# Superbot_USB.net
KiCad netlist of a schematic drawn in Altium Designer
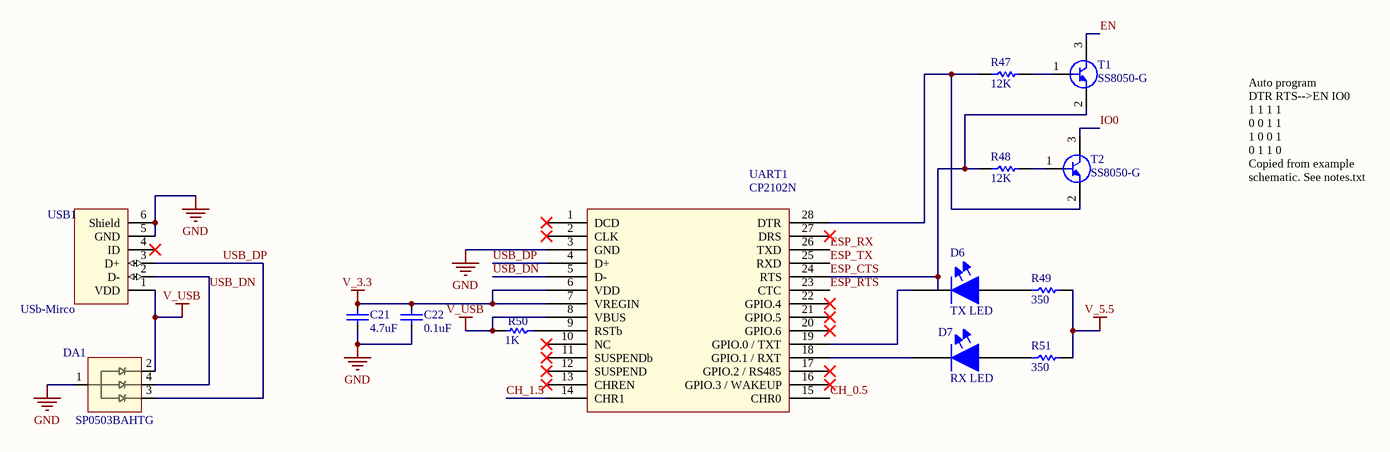
[diagram p0: Superbot_USB.SchDoc]

(export (version "E")
  (design (tool "Eeschema 10.0.6"))
  (components
    (comp (ref "C21")
      (value "4.7uF")
      (footprint "CAP0603R")
      (description "Capacitor")
      (fields
        (field (name "MANUFACTURER") "Microchip Technology")
        (field (name "MANUFACTURER PART NUM") "MIC5378YC5-TR")
      )
      (libsource (lib "SuperBot_Schlib1") (part "C"))
    )
    (comp (ref "C22")
      (value "0.1uF")
      (footprint "CAP0603R")
      (description "Capacitor")
      (fields
        (field (name "MANUFACTURER") "Microchip Technology")
        (field (name "MANUFACTURER PART NUM") "MIC5378YC5-TR")
      )
      (libsource (lib "SuperBot_Schlib1") (part "C"))
    )
    (comp (ref "D6")
      (value "TX LED")
      (footprint "0603_LED")
      (description "LED")
      (libsource (lib "SuperBot_Schlib1") (part "LED"))
    )
    (comp (ref "D7")
      (value "RX LED")
      (footprint "0603_LED")
      (description "LED")
      (libsource (lib "SuperBot_Schlib1") (part "LED"))
    )
    (comp (ref "DA1")
      (value "SP0503BAHTG")
      (footprint "SOT143_SP0503BAHT")
      (description "TVS DIODE 5.5VWM 8.5VC SOT143")
      (fields (field (name "MANUFACTURER") "Littelfuse"))
      (libsource (lib "SuperBot_Schlib1") (part "SP0503BAHTG"))
    )
    (comp (ref "R47")
      (value "12K")
      (footprint "RES0603R")
      (description "Resistor")
      (libsource (lib "SuperBot_Schlib1") (part "R"))
    )
    (comp (ref "R48")
      (value "12K")
      (footprint "RES0603R")
      (description "Resistor")
      (libsource (lib "SuperBot_Schlib1") (part "R"))
    )
    (comp (ref "R49")
      (value "350")
      (footprint "RES0603R")
      (description "Resistor")
      (libsource (lib "SuperBot_Schlib1") (part "R"))
    )
    (comp (ref "R50")
      (value "1K")
      (footprint "RES0603R")
      (description "Resistor")
      (libsource (lib "SuperBot_Schlib1") (part "R"))
    )
    (comp (ref "R51")
      (value "350")
      (footprint "RES0603R")
      (description "Resistor")
      (libsource (lib "SuperBot_Schlib1") (part "R"))
    )
    (comp (ref "T1")
      (value "SS8050-G")
      (footprint "SOT23-SS8050-G")
      (libsource (lib "SuperBot_Schlib1") (part "NPN Transistor"))
    )
    (comp (ref "T2")
      (value "SS8050-G")
      (footprint "SOT23-SS8050-G")
      (libsource (lib "SuperBot_Schlib1") (part "NPN Transistor"))
    )
    (comp (ref "UART1")
      (value "CP2102N")
      (footprint "QFN28_CP2102n")
      (description "336-3694-ND\r\n, IC BRIDGE USB TO UART 28QFN")
      (libsource (lib "SuperBot_Schlib1") (part "CP2102N"))
    )
    (comp (ref "USB1")
      (value "USb-Mirco")
      (footprint "USB_micro_through")
      (description "USb-Mirco, CONN RCPT MCR USB B SMD TH SHLL")
      (fields (field (name "MANUFACTURER PART NUM") "ZX62D-B-5P8") (field (name "MANUFACTURER") "Hirose"))
      (libsource (lib "SuperBot_Schlib1") (part "USb-Mirco"))
    )
  )
  (nets
    (net (code "1") (name "/CH_0.5") (class "Default")
      (node (ref "UART1") (pin "15") (pinfunction "CHR0_15") (pintype "passive"))
    )
    (net (code "2") (name "/CH_1.5") (class "Default")
      (node (ref "UART1") (pin "14") (pinfunction "CHR1_14") (pintype "passive"))
    )
    (net (code "3") (name "/EN") (class "Default")
      (node (ref "T1") (pin "3") (pinfunction "CLCTR_3") (pintype "passive"))
    )
    (net (code "4") (name "/ESP_CTS") (class "Default")
      (node (ref "R48") (pin "1") (pintype "passive"))
      (node (ref "T1") (pin "2") (pinfunction "EMTTR_2") (pintype "passive"))
      (node (ref "UART1") (pin "24") (pinfunction "RTS_24") (pintype "passive"))
    )
    (net (code "5") (name "/ESP_RTS") (class "Default")
      (node (ref "UART1") (pin "23") (pinfunction "CTC_23") (pintype "passive"))
    )
    (net (code "6") (name "/ESP_RX") (class "Default")
      (node (ref "UART1") (pin "26") (pinfunction "TXD_26") (pintype "passive"))
    )
    (net (code "7") (name "/ESP_TX") (class "Default")
      (node (ref "UART1") (pin "25") (pinfunction "RXD_25") (pintype "passive"))
    )
    (net (code "8") (name "/IO0") (class "Default")
      (node (ref "T2") (pin "3") (pinfunction "CLCTR_3") (pintype "passive"))
    )
    (net (code "9") (name "/USB_DN") (class "Default")
      (node (ref "DA1") (pin "4") (pinfunction "C_4") (pintype "passive"))
      (node (ref "UART1") (pin "5") (pinfunction "D-_5") (pintype "passive"))
      (node (ref "USB1") (pin "2") (pinfunction "D-_2") (pintype "bidirectional"))
    )
    (net (code "10") (name "/USB_DP") (class "Default")
      (node (ref "DA1") (pin "3") (pinfunction "B_3") (pintype "passive"))
      (node (ref "UART1") (pin "4") (pinfunction "D+_4") (pintype "passive"))
      (node (ref "USB1") (pin "3") (pinfunction "D+_3") (pintype "bidirectional"))
    )
    (net (code "11") (name "GND") (class "Default")
      (node (ref "C21") (pin "2") (pinfunction "2_2") (pintype "passive"))
      (node (ref "C22") (pin "2") (pinfunction "2_2") (pintype "passive"))
      (node (ref "DA1") (pin "1") (pinfunction "GND_1") (pintype "passive"))
      (node (ref "UART1") (pin "3") (pinfunction "GND_3") (pintype "passive"))
      (node (ref "USB1") (pin "5") (pinfunction "GND_5") (pintype "power_in"))
      (node (ref "USB1") (pin "6") (pinfunction "Shield_6") (pintype "passive"))
    )
    (net (code "12") (name "Net-(D6-ANODE)") (class "Default")
      (node (ref "D6") (pin "A") (pinfunction "ANODE_A") (pintype "passive"))
      (node (ref "R49") (pin "1") (pintype "passive"))
    )
    (net (code "13") (name "Net-(D6-CATHODE)") (class "Default")
      (node (ref "D6") (pin "K") (pinfunction "CATHODE_K") (pintype "passive"))
      (node (ref "UART1") (pin "19") (pinfunction "GPIO.0_/_TXT_19") (pintype "passive"))
    )
    (net (code "14") (name "Net-(D7-ANODE)") (class "Default")
      (node (ref "D7") (pin "A") (pinfunction "ANODE_A") (pintype "passive"))
      (node (ref "R51") (pin "1") (pintype "passive"))
    )
    (net (code "15") (name "Net-(D7-CATHODE)") (class "Default")
      (node (ref "D7") (pin "K") (pinfunction "CATHODE_K") (pintype "passive"))
      (node (ref "UART1") (pin "18") (pinfunction "GPIO.1_/_RXT_18") (pintype "passive"))
    )
    (net (code "16") (name "Net-(T1-BASE)") (class "Default")
      (node (ref "R47") (pin "2") (pintype "passive"))
      (node (ref "T1") (pin "1") (pinfunction "BASE_1") (pintype "passive"))
    )
    (net (code "17") (name "Net-(T2-BASE)") (class "Default")
      (node (ref "R48") (pin "2") (pintype "passive"))
      (node (ref "T2") (pin "1") (pinfunction "BASE_1") (pintype "passive"))
    )
    (net (code "18") (name "Net-(T2-EMTTR)") (class "Default")
      (node (ref "R47") (pin "1") (pintype "passive"))
      (node (ref "T2") (pin "2") (pinfunction "EMTTR_2") (pintype "passive"))
      (node (ref "UART1") (pin "28") (pinfunction "DTR_28") (pintype "passive"))
    )
    (net (code "19") (name "Net-(UART1-RSTb)") (class "Default")
      (node (ref "R50") (pin "1") (pintype "passive"))
      (node (ref "UART1") (pin "9") (pinfunction "RSTb_9") (pintype "passive"))
    )
    (net (code "20") (name "V_3.3") (class "Default")
      (node (ref "C21") (pin "1") (pinfunction "1_1") (pintype "passive"))
      (node (ref "C22") (pin "1") (pinfunction "1_1") (pintype "passive"))
      (node (ref "UART1") (pin "6") (pinfunction "VDD_6") (pintype "passive"))
      (node (ref "UART1") (pin "7") (pinfunction "VREGIN_7") (pintype "passive"))
    )
    (net (code "21") (name "V_5.5") (class "Default")
      (node (ref "R49") (pin "2") (pintype "passive"))
      (node (ref "R51") (pin "2") (pintype "passive"))
    )
    (net (code "22") (name "V_USB") (class "Default")
      (node (ref "DA1") (pin "2") (pinfunction "A_2") (pintype "passive"))
      (node (ref "R50") (pin "2") (pintype "passive"))
      (node (ref "UART1") (pin "8") (pinfunction "VBUS_8") (pintype "passive"))
      (node (ref "USB1") (pin "1") (pinfunction "VDD_1") (pintype "power_in"))
    )
    (net (code "23") (name "unconnected-(UART1-CHREN-Pad13)") (class "Default")
      (node (ref "UART1") (pin "13") (pinfunction "CHREN_13") (pintype "passive+no_connect"))
    )
    (net (code "24") (name "unconnected-(UART1-CLK-Pad2)") (class "Default")
      (node (ref "UART1") (pin "2") (pinfunction "CLK_2") (pintype "passive+no_connect"))
    )
    (net (code "25") (name "unconnected-(UART1-DCD-Pad1)") (class "Default")
      (node (ref "UART1") (pin "1") (pinfunction "DCD_1") (pintype "passive+no_connect"))
    )
    (net (code "26") (name "unconnected-(UART1-DRS-Pad27)") (class "Default")
      (node (ref "UART1") (pin "27") (pinfunction "DRS_27") (pintype "passive+no_connect"))
    )
    (net (code "27") (name "unconnected-(UART1-GPIO.2_{slash}_RS485-Pad17)") (class "Default")
      (node (ref "UART1") (pin "17") (pinfunction "GPIO.2_/_RS485_17") (pintype "passive+no_connect"))
    )
    (net (code "28") (name "unconnected-(UART1-GPIO.3_{slash}_WAKEUP-Pad16)") (class "Default")
      (node (ref "UART1") (pin "16") (pinfunction "GPIO.3_/_WAKEUP_16") (pintype "passive+no_connect"))
    )
    (net (code "29") (name "unconnected-(UART1-GPIO.4-Pad22)") (class "Default")
      (node (ref "UART1") (pin "22") (pinfunction "GPIO.4_22") (pintype "passive+no_connect"))
    )
    (net (code "30") (name "unconnected-(UART1-GPIO.5-Pad21)") (class "Default")
      (node (ref "UART1") (pin "21") (pinfunction "GPIO.5_21") (pintype "passive+no_connect"))
    )
    (net (code "31") (name "unconnected-(UART1-GPIO.6-Pad20)") (class "Default")
      (node (ref "UART1") (pin "20") (pinfunction "GPIO.6_20") (pintype "passive+no_connect"))
    )
    (net (code "32") (name "unconnected-(UART1-NC-Pad10)") (class "Default")
      (node (ref "UART1") (pin "10") (pinfunction "NC_10") (pintype "passive+no_connect"))
    )
    (net (code "33") (name "unconnected-(UART1-SUSPEND-Pad12)") (class "Default")
      (node (ref "UART1") (pin "12") (pinfunction "SUSPEND_12") (pintype "passive+no_connect"))
    )
    (net (code "34") (name "unconnected-(UART1-SUSPENDb-Pad11)") (class "Default")
      (node (ref "UART1") (pin "11") (pinfunction "SUSPENDb_11") (pintype "passive+no_connect"))
    )
    (net (code "35") (name "unconnected-(USB1-ID-Pad4)") (class "Default")
      (node (ref "USB1") (pin "4") (pinfunction "ID_4") (pintype "passive+no_connect"))
    )
  )
)
